# POSCON_PCB.net
KiCad netlist of a schematic drawn in EAGLE
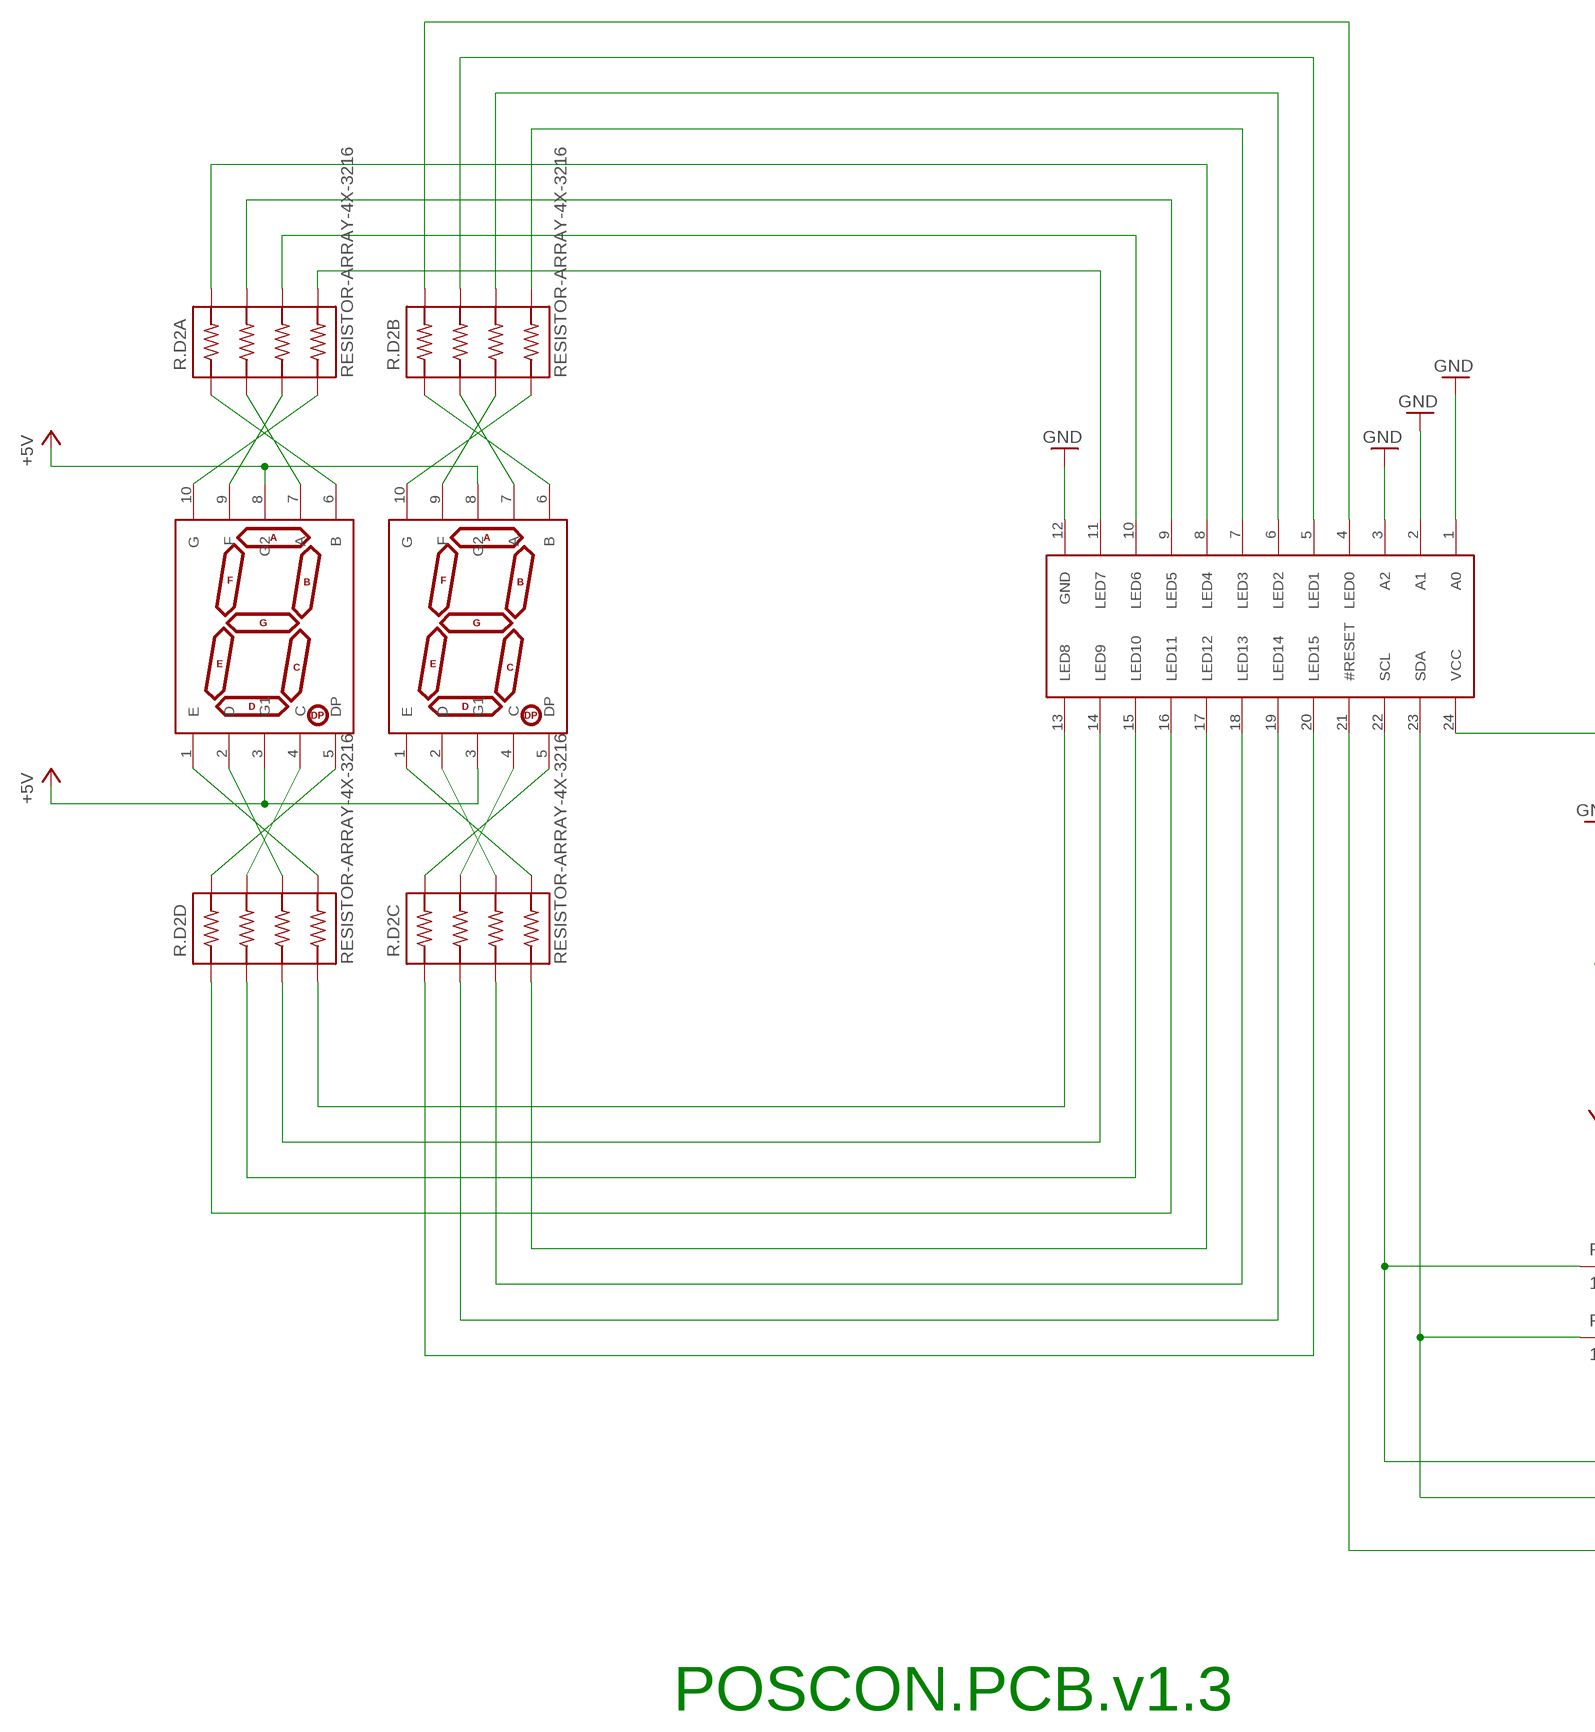
[diagram p0: schematic, sheet 1, part 1 of 2]
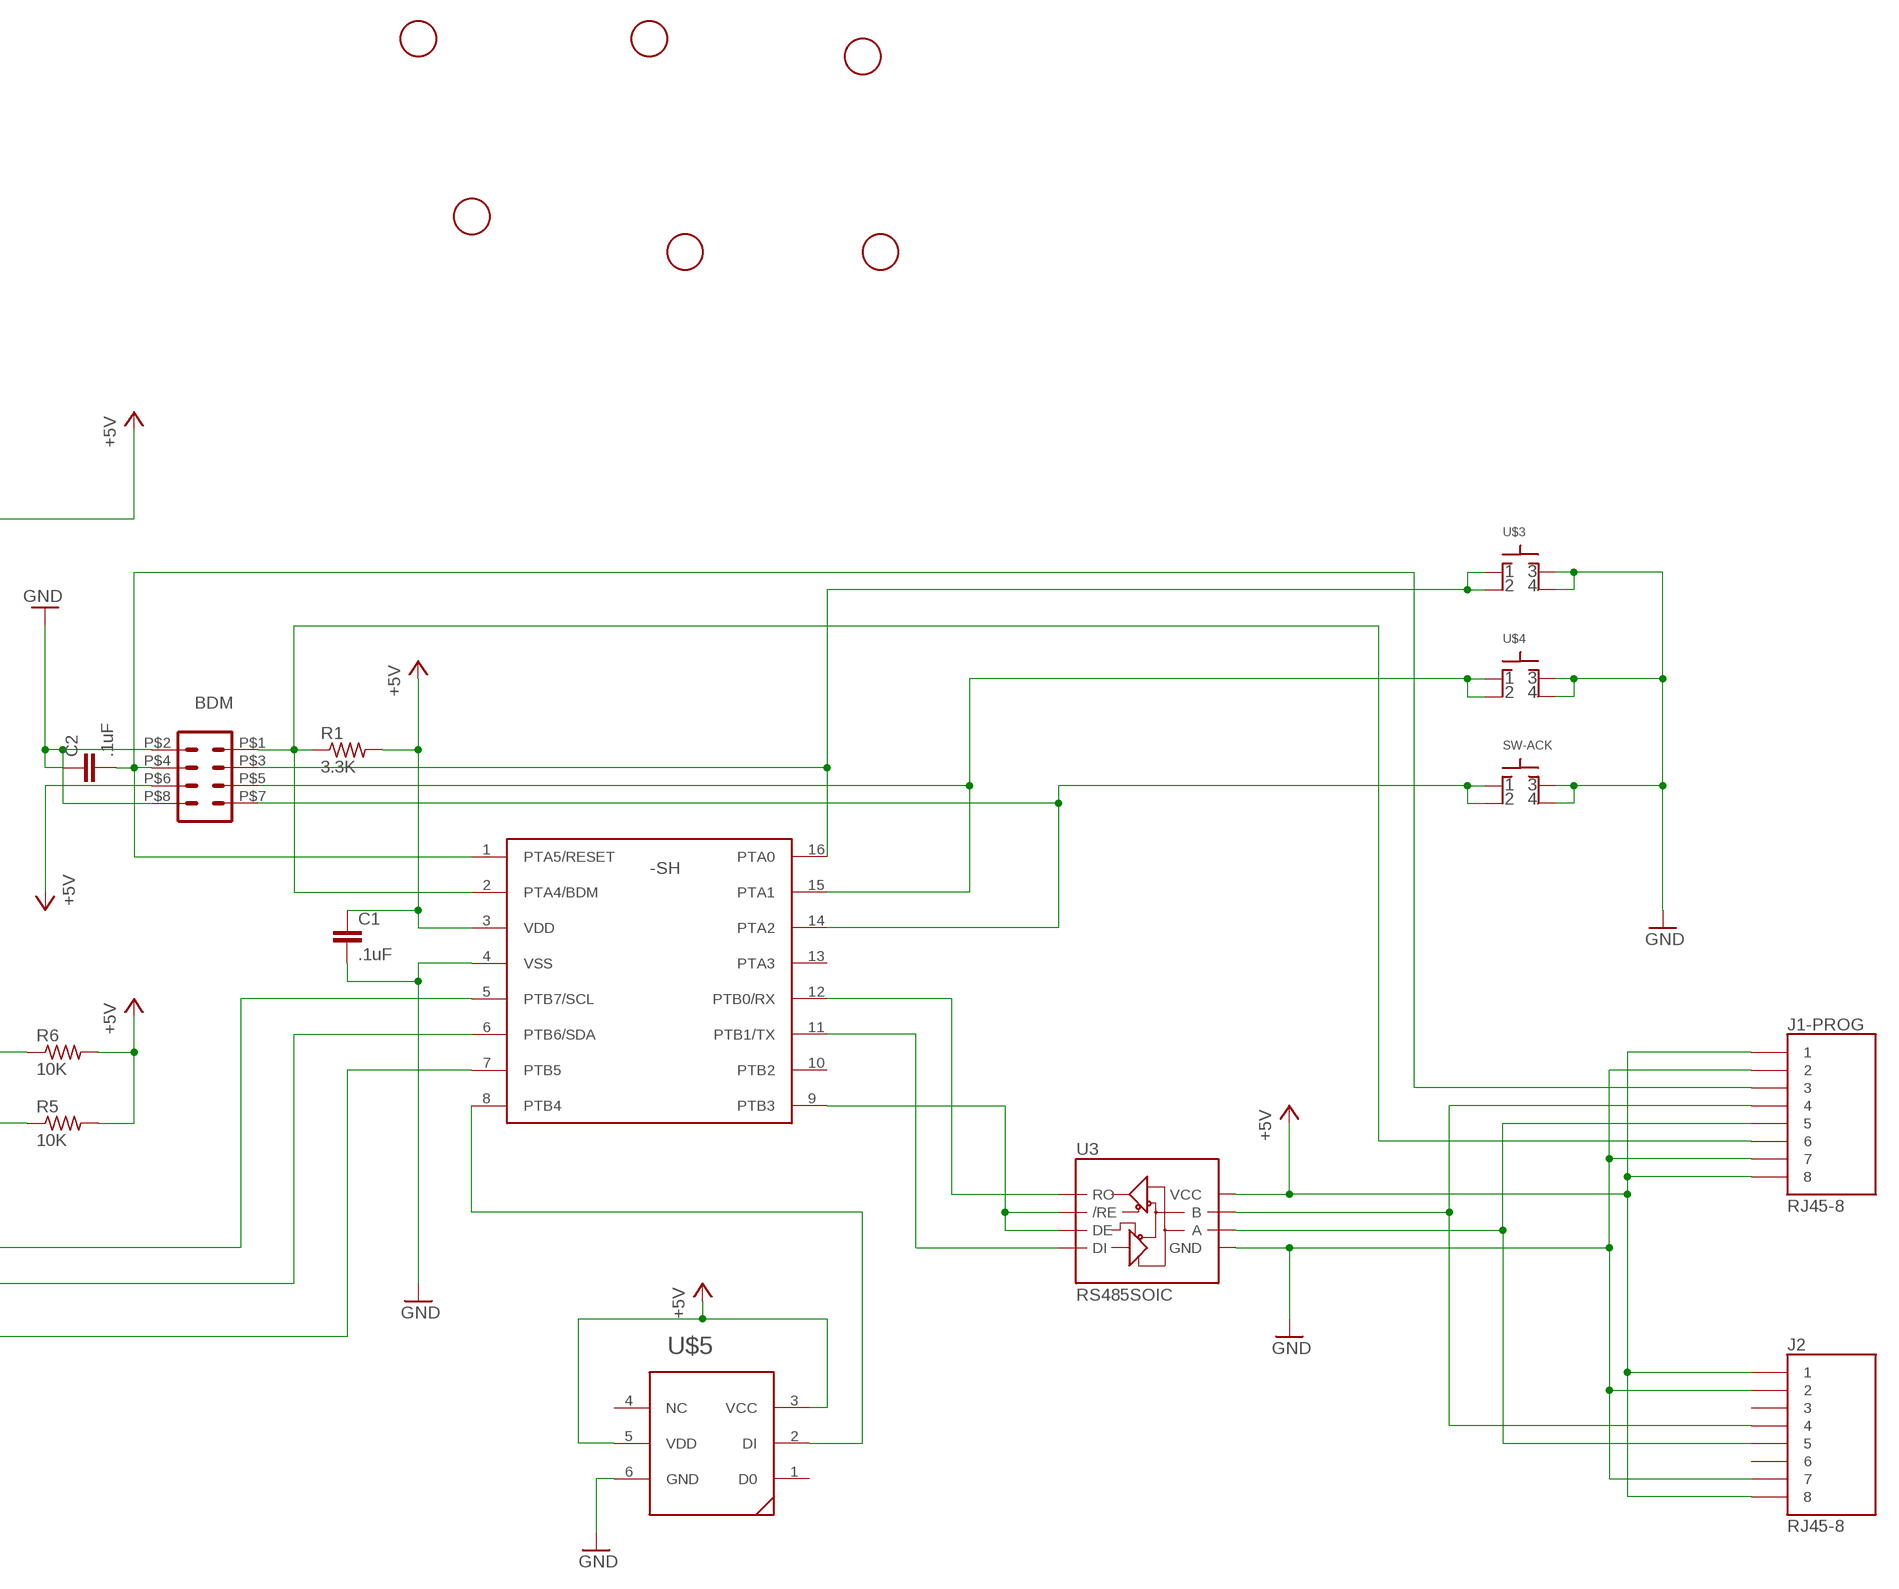
[diagram p1: schematic, sheet 1, part 2 of 2]

(export (version "E")
  (design (tool "Eeschema 10.0.6"))
  (components
    (comp (ref "BDM")
      (value "TP2X4SMD")
      (footprint "eagle-import:SMD4X2")
      (libsource (lib "eagle-import") (part "TP2X4SMD"))
    )
    (comp (ref "C1")
      (value ".1uF")
      (footprint "eagle-import:C0402")
      (libsource (lib "eagle-import") (part "RF-C0402"))
    )
    (comp (ref "C2")
      (value ".1uF")
      (footprint "eagle-import:C0402")
      (libsource (lib "eagle-import") (part "RF-C0402"))
    )
    (comp (ref "J1-PROG")
      (value "RJ45-8")
      (footprint "eagle-import:RJ45_SMD")
      (fields (field (name "MFGN") "Molex") (field (name "MFGP") "0955016889"))
      (libsource (lib "eagle-import") (part "RJ45-8"))
    )
    (comp (ref "J2")
      (value "RJ45-8")
      (footprint "eagle-import:RJ45_SMD")
      (fields (field (name "MFGN") "Molex") (field (name "MFGP") "0955016889"))
      (libsource (lib "eagle-import") (part "RJ45-8"))
    )
    (comp (ref "LED1")
      (value "7SEGMENT-1DIGITSMD")
      (footprint "eagle-import:7SEGMENT-1DIG-.40-SMD")
      (libsource (lib "eagle-import") (part "7SEGMENT-1DIGITSMD"))
    )
    (comp (ref "LED2")
      (value "7SEGMENT-1DIGITSMD")
      (footprint "eagle-import:7SEGMENT-1DIG-.40-SMD")
      (libsource (lib "eagle-import") (part "7SEGMENT-1DIGITSMD"))
    )
    (comp (ref "R.D2A")
      (value "RESISTOR-ARRAY-4X-3216")
      (footprint "eagle-import:3216-4X")
      (libsource (lib "eagle-import") (part "RESISTOR-ARRAY-4X-3216"))
    )
    (comp (ref "R.D2B")
      (value "RESISTOR-ARRAY-4X-3216")
      (footprint "eagle-import:3216-4X")
      (libsource (lib "eagle-import") (part "RESISTOR-ARRAY-4X-3216"))
    )
    (comp (ref "R.D2C")
      (value "RESISTOR-ARRAY-4X-3216")
      (footprint "eagle-import:3216-4X")
      (libsource (lib "eagle-import") (part "RESISTOR-ARRAY-4X-3216"))
    )
    (comp (ref "R.D2D")
      (value "RESISTOR-ARRAY-4X-3216")
      (footprint "eagle-import:3216-4X")
      (libsource (lib "eagle-import") (part "RESISTOR-ARRAY-4X-3216"))
    )
    (comp (ref "R1")
      (value "3.3K")
      (footprint "eagle-import:RF-R0402")
      (libsource (lib "eagle-import") (part "RF-R0402"))
    )
    (comp (ref "R5")
      (value "10K")
      (footprint "eagle-import:RF-R0402")
      (libsource (lib "eagle-import") (part "RF-R0402"))
    )
    (comp (ref "R6")
      (value "10K")
      (footprint "eagle-import:RF-R0402")
      (libsource (lib "eagle-import") (part "RF-R0402"))
    )
    (comp (ref "SW-ACK")
      (value "SWITCH-TACTILE-320.01E11WHT")
      (footprint "eagle-import:SWITCH-TACTILE-320.01E11WHT")
      (fields (field (name "MFGP") "320.01E11WHT"))
      (libsource (lib "eagle-import") (part "SWITCH-TACTILE-320.01E11WHT"))
    )
    (comp (ref "U$1")
      (value "FIDUCIAL")
      (footprint "eagle-import:FIDUCIAL_1MM")
      (libsource (lib "eagle-import") (part "FIDUCIAL"))
    )
    (comp (ref "U$2")
      (value "FIDUCIAL")
      (footprint "eagle-import:FIDUCIAL_1MM")
      (libsource (lib "eagle-import") (part "FIDUCIAL"))
    )
    (comp (ref "U$3")
      (value "SWITCH-TACTILE")
      (footprint "eagle-import:ESWITCH-TL3301PF")
      (libsource (lib "eagle-import") (part "SWITCH-TACTILE"))
    )
    (comp (ref "U$4")
      (value "SWITCH-TACTILE")
      (footprint "eagle-import:ESWITCH-TL3301PF")
      (libsource (lib "eagle-import") (part "SWITCH-TACTILE"))
    )
    (comp (ref "U$5")
      (value "WS2812")
      (footprint "eagle-import:PLCC-6")
      (libsource (lib "eagle-import") (part "WS2812"))
    )
    (comp (ref "U$6")
      (value "FIDUCIAL")
      (footprint "eagle-import:FIDUCIAL_1MM")
      (libsource (lib "eagle-import") (part "FIDUCIAL"))
    )
    (comp (ref "U$7")
      (value "FIDUCIAL")
      (footprint "eagle-import:FIDUCIAL_1MM")
      (libsource (lib "eagle-import") (part "FIDUCIAL"))
    )
    (comp (ref "U$8")
      (value "FIDUCIAL")
      (footprint "eagle-import:FIDUCIAL_1MM")
      (libsource (lib "eagle-import") (part "FIDUCIAL"))
    )
    (comp (ref "U$9")
      (value "FIDUCIAL")
      (footprint "eagle-import:FIDUCIAL_1MM")
      (libsource (lib "eagle-import") (part "FIDUCIAL"))
    )
    (comp (ref "U1")
      (value "MC9S08SH8CTG")
      (footprint "eagle-import:TSSOP16")
      (libsource (lib "eagle-import") (part "MC9S08SH8CTG"))
    )
    (comp (ref "U3")
      (value "RS485SOIC")
      (footprint "eagle-import:SO08")
      (libsource (lib "eagle-import") (part "RS485SOIC"))
    )
    (comp (ref "U4")
      (value "PCA9552")
      (footprint "eagle-import:TSSOP24")
      (fields (field (name "MFGP") "PCA9552PW,112"))
      (libsource (lib "eagle-import") (part "PCA9552"))
    )
  )
  (nets
    (net (code "1") (name "+5V") (class "Default")
      (node (ref "BDM") (pin "P$6") (pinfunction "6_P$6") (pintype "passive"))
      (node (ref "C1") (pin "1") (pinfunction "1_1") (pintype "passive"))
      (node (ref "J1-PROG") (pin "P$1") (pinfunction "1_P$1") (pintype "bidirectional"))
      (node (ref "J1-PROG") (pin "P$8") (pinfunction "8_P$8") (pintype "bidirectional"))
      (node (ref "J2") (pin "P$1") (pinfunction "1_P$1") (pintype "bidirectional"))
      (node (ref "J2") (pin "P$8") (pinfunction "8_P$8") (pintype "bidirectional"))
      (node (ref "LED1") (pin "3") (pinfunction "G1_3") (pintype "bidirectional"))
      (node (ref "LED1") (pin "8") (pinfunction "G2_8") (pintype "bidirectional"))
      (node (ref "LED2") (pin "3") (pinfunction "G1_3") (pintype "bidirectional"))
      (node (ref "LED2") (pin "8") (pinfunction "G2_8") (pintype "bidirectional"))
      (node (ref "R1") (pin "2") (pinfunction "2_2") (pintype "passive"))
      (node (ref "R5") (pin "2") (pinfunction "2_2") (pintype "passive"))
      (node (ref "R6") (pin "2") (pinfunction "2_2") (pintype "passive"))
      (node (ref "U$5") (pin "3") (pinfunction "VCC_3") (pintype "bidirectional"))
      (node (ref "U$5") (pin "5") (pinfunction "VDD_5") (pintype "bidirectional"))
      (node (ref "U1") (pin "3") (pinfunction "VDD_3") (pintype "bidirectional"))
      (node (ref "U3") (pin "8") (pinfunction "VCC_8") (pintype "bidirectional"))
      (node (ref "U4") (pin "24") (pinfunction "VCC_24") (pintype "bidirectional"))
    )
    (net (code "2") (name "GND") (class "Default")
      (node (ref "BDM") (pin "P$2") (pinfunction "2_P$2") (pintype "passive"))
      (node (ref "BDM") (pin "P$8") (pinfunction "8_P$8") (pintype "passive"))
      (node (ref "C1") (pin "2") (pinfunction "2_2") (pintype "passive"))
      (node (ref "C2") (pin "1") (pinfunction "1_1") (pintype "passive"))
      (node (ref "J1-PROG") (pin "P$2") (pinfunction "2_P$2") (pintype "bidirectional"))
      (node (ref "J1-PROG") (pin "P$7") (pinfunction "7_P$7") (pintype "bidirectional"))
      (node (ref "J2") (pin "P$2") (pinfunction "2_P$2") (pintype "bidirectional"))
      (node (ref "J2") (pin "P$7") (pinfunction "7_P$7") (pintype "bidirectional"))
      (node (ref "SW-ACK") (pin "P$3") (pinfunction "3_P$3") (pintype "input"))
      (node (ref "SW-ACK") (pin "P$4") (pinfunction "4_P$4") (pintype "input"))
      (node (ref "U$3") (pin "3") (pinfunction "3_3") (pintype "input"))
      (node (ref "U$3") (pin "4") (pinfunction "4_4") (pintype "input"))
      (node (ref "U$4") (pin "3") (pinfunction "3_3") (pintype "input"))
      (node (ref "U$4") (pin "4") (pinfunction "4_4") (pintype "input"))
      (node (ref "U$5") (pin "6") (pinfunction "GND_6") (pintype "bidirectional"))
      (node (ref "U1") (pin "4") (pinfunction "VSS_4") (pintype "bidirectional"))
      (node (ref "U3") (pin "5") (pinfunction "GND_5") (pintype "bidirectional"))
      (node (ref "U4") (pin "1") (pinfunction "A0_1") (pintype "bidirectional"))
      (node (ref "U4") (pin "12") (pinfunction "GND_12") (pintype "bidirectional"))
      (node (ref "U4") (pin "2") (pinfunction "A1_2") (pintype "bidirectional"))
      (node (ref "U4") (pin "3") (pinfunction "A2_3") (pintype "bidirectional"))
    )
    (net (code "3") (name "Net-(BDM-1)") (class "Default")
      (node (ref "BDM") (pin "P$1") (pinfunction "1_P$1") (pintype "passive"))
      (node (ref "J1-PROG") (pin "P$6") (pinfunction "6_P$6") (pintype "bidirectional"))
      (node (ref "R1") (pin "1") (pinfunction "1_1") (pintype "passive"))
      (node (ref "U1") (pin "2") (pinfunction "PTA4/BDM_2") (pintype "bidirectional"))
    )
    (net (code "4") (name "Net-(BDM-3)") (class "Default")
      (node (ref "BDM") (pin "P$3") (pinfunction "3_P$3") (pintype "passive"))
      (node (ref "U$3") (pin "1") (pinfunction "1_1") (pintype "input"))
      (node (ref "U$3") (pin "2") (pinfunction "2_2") (pintype "input"))
      (node (ref "U1") (pin "16") (pinfunction "PTA0_16") (pintype "bidirectional"))
    )
    (net (code "5") (name "Net-(BDM-4)") (class "Default")
      (node (ref "BDM") (pin "P$4") (pinfunction "4_P$4") (pintype "passive"))
      (node (ref "C2") (pin "2") (pinfunction "2_2") (pintype "passive"))
      (node (ref "J1-PROG") (pin "P$3") (pinfunction "3_P$3") (pintype "bidirectional"))
      (node (ref "U1") (pin "1") (pinfunction "PTA5/RESET_1") (pintype "bidirectional"))
    )
    (net (code "6") (name "Net-(BDM-5)") (class "Default")
      (node (ref "BDM") (pin "P$5") (pinfunction "5_P$5") (pintype "passive"))
      (node (ref "U$4") (pin "1") (pinfunction "1_1") (pintype "input"))
      (node (ref "U$4") (pin "2") (pinfunction "2_2") (pintype "input"))
      (node (ref "U1") (pin "15") (pinfunction "PTA1_15") (pintype "bidirectional"))
    )
    (net (code "7") (name "Net-(BDM-7)") (class "Default")
      (node (ref "BDM") (pin "P$7") (pinfunction "7_P$7") (pintype "passive"))
      (node (ref "SW-ACK") (pin "P$1") (pinfunction "1_P$1") (pintype "input"))
      (node (ref "SW-ACK") (pin "P$2") (pinfunction "2_P$2") (pintype "input"))
      (node (ref "U1") (pin "14") (pinfunction "PTA2_14") (pintype "bidirectional"))
    )
    (net (code "8") (name "Net-(J1-PROG-4)") (class "Default")
      (node (ref "J1-PROG") (pin "P$4") (pinfunction "4_P$4") (pintype "bidirectional"))
      (node (ref "J2") (pin "P$4") (pinfunction "4_P$4") (pintype "bidirectional"))
      (node (ref "U3") (pin "7") (pinfunction "B_7") (pintype "bidirectional"))
    )
    (net (code "9") (name "Net-(J1-PROG-5)") (class "Default")
      (node (ref "J1-PROG") (pin "P$5") (pinfunction "5_P$5") (pintype "bidirectional"))
      (node (ref "J2") (pin "P$5") (pinfunction "5_P$5") (pintype "bidirectional"))
      (node (ref "U3") (pin "6") (pinfunction "A_6") (pintype "bidirectional"))
    )
    (net (code "10") (name "Net-(LED1-A)") (class "Default")
      (node (ref "LED1") (pin "7") (pinfunction "A_7") (pintype "bidirectional"))
      (node (ref "R.D2B") (pin "2") (pinfunction "2A_2") (pintype "passive"))
    )
    (net (code "11") (name "Net-(LED1-B)") (class "Default")
      (node (ref "LED1") (pin "6") (pinfunction "B_6") (pintype "bidirectional"))
      (node (ref "R.D2B") (pin "1") (pinfunction "1A_1") (pintype "passive"))
    )
    (net (code "12") (name "Net-(LED1-C)") (class "Default")
      (node (ref "LED1") (pin "4") (pinfunction "C_4") (pintype "bidirectional"))
      (node (ref "R.D2C") (pin "7") (pinfunction "2B_7") (pintype "passive"))
    )
    (net (code "13") (name "Net-(LED1-D)") (class "Default")
      (node (ref "LED1") (pin "2") (pinfunction "D_2") (pintype "bidirectional"))
      (node (ref "R.D2C") (pin "6") (pinfunction "3B_6") (pintype "passive"))
    )
    (net (code "14") (name "Net-(LED1-DP)") (class "Default")
      (node (ref "LED1") (pin "5") (pinfunction "DP_5") (pintype "bidirectional"))
      (node (ref "R.D2C") (pin "8") (pinfunction "1B_8") (pintype "passive"))
    )
    (net (code "15") (name "Net-(LED1-E)") (class "Default")
      (node (ref "LED1") (pin "1") (pinfunction "E_1") (pintype "bidirectional"))
      (node (ref "R.D2C") (pin "5") (pinfunction "4B_5") (pintype "passive"))
    )
    (net (code "16") (name "Net-(LED1-F)") (class "Default")
      (node (ref "LED1") (pin "9") (pinfunction "F_9") (pintype "bidirectional"))
      (node (ref "R.D2B") (pin "3") (pinfunction "3A_3") (pintype "passive"))
    )
    (net (code "17") (name "Net-(LED1-G)") (class "Default")
      (node (ref "LED1") (pin "10") (pinfunction "G_10") (pintype "bidirectional"))
      (node (ref "R.D2B") (pin "4") (pinfunction "4A_4") (pintype "passive"))
    )
    (net (code "18") (name "Net-(LED2-A)") (class "Default")
      (node (ref "LED2") (pin "7") (pinfunction "A_7") (pintype "bidirectional"))
      (node (ref "R.D2A") (pin "2") (pinfunction "2A_2") (pintype "passive"))
    )
    (net (code "19") (name "Net-(LED2-B)") (class "Default")
      (node (ref "LED2") (pin "6") (pinfunction "B_6") (pintype "bidirectional"))
      (node (ref "R.D2A") (pin "1") (pinfunction "1A_1") (pintype "passive"))
    )
    (net (code "20") (name "Net-(LED2-C)") (class "Default")
      (node (ref "LED2") (pin "4") (pinfunction "C_4") (pintype "bidirectional"))
      (node (ref "R.D2D") (pin "7") (pinfunction "2B_7") (pintype "passive"))
    )
    (net (code "21") (name "Net-(LED2-D)") (class "Default")
      (node (ref "LED2") (pin "2") (pinfunction "D_2") (pintype "bidirectional"))
      (node (ref "R.D2D") (pin "6") (pinfunction "3B_6") (pintype "passive"))
    )
    (net (code "22") (name "Net-(LED2-DP)") (class "Default")
      (node (ref "LED2") (pin "5") (pinfunction "DP_5") (pintype "bidirectional"))
      (node (ref "R.D2D") (pin "8") (pinfunction "1B_8") (pintype "passive"))
    )
    (net (code "23") (name "Net-(LED2-E)") (class "Default")
      (node (ref "LED2") (pin "1") (pinfunction "E_1") (pintype "bidirectional"))
      (node (ref "R.D2D") (pin "5") (pinfunction "4B_5") (pintype "passive"))
    )
    (net (code "24") (name "Net-(LED2-F)") (class "Default")
      (node (ref "LED2") (pin "9") (pinfunction "F_9") (pintype "bidirectional"))
      (node (ref "R.D2A") (pin "3") (pinfunction "3A_3") (pintype "passive"))
    )
    (net (code "25") (name "Net-(LED2-G)") (class "Default")
      (node (ref "LED2") (pin "10") (pinfunction "G_10") (pintype "bidirectional"))
      (node (ref "R.D2A") (pin "4") (pinfunction "4A_4") (pintype "passive"))
    )
    (net (code "26") (name "Net-(R.D2A-1B)") (class "Default")
      (node (ref "R.D2A") (pin "8") (pinfunction "1B_8") (pintype "passive"))
      (node (ref "U4") (pin "8") (pinfunction "LED4_8") (pintype "bidirectional"))
    )
    (net (code "27") (name "Net-(R.D2A-2B)") (class "Default")
      (node (ref "R.D2A") (pin "7") (pinfunction "2B_7") (pintype "passive"))
      (node (ref "U4") (pin "9") (pinfunction "LED5_9") (pintype "bidirectional"))
    )
    (net (code "28") (name "Net-(R.D2A-3B)") (class "Default")
      (node (ref "R.D2A") (pin "6") (pinfunction "3B_6") (pintype "passive"))
      (node (ref "U4") (pin "10") (pinfunction "LED6_10") (pintype "bidirectional"))
    )
    (net (code "29") (name "Net-(R.D2A-4B)") (class "Default")
      (node (ref "R.D2A") (pin "5") (pinfunction "4B_5") (pintype "passive"))
      (node (ref "U4") (pin "11") (pinfunction "LED7_11") (pintype "bidirectional"))
    )
    (net (code "30") (name "Net-(R.D2B-1B)") (class "Default")
      (node (ref "R.D2B") (pin "8") (pinfunction "1B_8") (pintype "passive"))
      (node (ref "U4") (pin "4") (pinfunction "LED0_4") (pintype "bidirectional"))
    )
    (net (code "31") (name "Net-(R.D2B-2B)") (class "Default")
      (node (ref "R.D2B") (pin "7") (pinfunction "2B_7") (pintype "passive"))
      (node (ref "U4") (pin "5") (pinfunction "LED1_5") (pintype "bidirectional"))
    )
    (net (code "32") (name "Net-(R.D2B-3B)") (class "Default")
      (node (ref "R.D2B") (pin "6") (pinfunction "3B_6") (pintype "passive"))
      (node (ref "U4") (pin "6") (pinfunction "LED2_6") (pintype "bidirectional"))
    )
    (net (code "33") (name "Net-(R.D2B-4B)") (class "Default")
      (node (ref "R.D2B") (pin "5") (pinfunction "4B_5") (pintype "passive"))
      (node (ref "U4") (pin "7") (pinfunction "LED3_7") (pintype "bidirectional"))
    )
    (net (code "34") (name "Net-(R.D2C-1A)") (class "Default")
      (node (ref "R.D2C") (pin "1") (pinfunction "1A_1") (pintype "passive"))
      (node (ref "U4") (pin "20") (pinfunction "LED15_20") (pintype "bidirectional"))
    )
    (net (code "35") (name "Net-(R.D2C-2A)") (class "Default")
      (node (ref "R.D2C") (pin "2") (pinfunction "2A_2") (pintype "passive"))
      (node (ref "U4") (pin "19") (pinfunction "LED14_19") (pintype "bidirectional"))
    )
    (net (code "36") (name "Net-(R.D2C-3A)") (class "Default")
      (node (ref "R.D2C") (pin "3") (pinfunction "3A_3") (pintype "passive"))
      (node (ref "U4") (pin "18") (pinfunction "LED13_18") (pintype "bidirectional"))
    )
    (net (code "37") (name "Net-(R.D2C-4A)") (class "Default")
      (node (ref "R.D2C") (pin "4") (pinfunction "4A_4") (pintype "passive"))
      (node (ref "U4") (pin "17") (pinfunction "LED12_17") (pintype "bidirectional"))
    )
    (net (code "38") (name "Net-(R.D2D-1A)") (class "Default")
      (node (ref "R.D2D") (pin "1") (pinfunction "1A_1") (pintype "passive"))
      (node (ref "U4") (pin "16") (pinfunction "LED11_16") (pintype "bidirectional"))
    )
    (net (code "39") (name "Net-(R.D2D-2A)") (class "Default")
      (node (ref "R.D2D") (pin "2") (pinfunction "2A_2") (pintype "passive"))
      (node (ref "U4") (pin "15") (pinfunction "LED10_15") (pintype "bidirectional"))
    )
    (net (code "40") (name "Net-(R.D2D-3A)") (class "Default")
      (node (ref "R.D2D") (pin "3") (pinfunction "3A_3") (pintype "passive"))
      (node (ref "U4") (pin "14") (pinfunction "LED9_14") (pintype "bidirectional"))
    )
    (net (code "41") (name "Net-(R.D2D-4A)") (class "Default")
      (node (ref "R.D2D") (pin "4") (pinfunction "4A_4") (pintype "passive"))
      (node (ref "U4") (pin "13") (pinfunction "LED8_13") (pintype "bidirectional"))
    )
    (net (code "42") (name "Net-(U$5-DI)") (class "Default")
      (node (ref "U$5") (pin "2") (pinfunction "DI_2") (pintype "bidirectional"))
      (node (ref "U1") (pin "8") (pinfunction "PTB4_8") (pintype "bidirectional"))
    )
    (net (code "43") (name "Net-(U1-PTB0{slash}RX)") (class "Default")
      (node (ref "U1") (pin "12") (pinfunction "PTB0/RX_12") (pintype "bidirectional"))
      (node (ref "U3") (pin "1") (pinfunction "RO_1") (pintype "bidirectional"))
    )
    (net (code "44") (name "Net-(U1-PTB1{slash}TX)") (class "Default")
      (node (ref "U1") (pin "11") (pinfunction "PTB1/TX_11") (pintype "bidirectional"))
      (node (ref "U3") (pin "4") (pinfunction "DI_4") (pintype "bidirectional"))
    )
    (net (code "45") (name "Net-(U1-PTB3)") (class "Default")
      (node (ref "U1") (pin "9") (pinfunction "PTB3_9") (pintype "bidirectional"))
      (node (ref "U3") (pin "2") (pinfunction "/RE_2") (pintype "bidirectional"))
      (node (ref "U3") (pin "3") (pinfunction "DE_3") (pintype "bidirectional"))
    )
    (net (code "46") (name "Net-(U1-PTB5)") (class "Default")
      (node (ref "U1") (pin "7") (pinfunction "PTB5_7") (pintype "bidirectional"))
      (node (ref "U4") (pin "21") (pinfunction "#RESET_21") (pintype "bidirectional"))
    )
    (net (code "47") (name "Net-(U1-PTB6{slash}SDA)") (class "Default")
      (node (ref "R5") (pin "1") (pinfunction "1_1") (pintype "passive"))
      (node (ref "U1") (pin "6") (pinfunction "PTB6/SDA_6") (pintype "bidirectional"))
      (node (ref "U4") (pin "23") (pinfunction "SDA_23") (pintype "bidirectional"))
    )
    (net (code "48") (name "Net-(U1-PTB7{slash}SCL)") (class "Default")
      (node (ref "R6") (pin "1") (pinfunction "1_1") (pintype "passive"))
      (node (ref "U1") (pin "5") (pinfunction "PTB7/SCL_5") (pintype "bidirectional"))
      (node (ref "U4") (pin "22") (pinfunction "SCL_22") (pintype "bidirectional"))
    )
    (net (code "49") (name "unconnected-(J2-3-PadP$3)") (class "Default")
      (node (ref "J2") (pin "P$3") (pinfunction "3_P$3") (pintype "bidirectional"))
    )
    (net (code "50") (name "unconnected-(J2-6-PadP$6)") (class "Default")
      (node (ref "J2") (pin "P$6") (pinfunction "6_P$6") (pintype "bidirectional"))
    )
    (net (code "51") (name "unconnected-(U$5-D0-Pad1)") (class "Default")
      (node (ref "U$5") (pin "1") (pinfunction "D0_1") (pintype "bidirectional"))
    )
    (net (code "52") (name "unconnected-(U$5-NC-Pad4)") (class "Default")
      (node (ref "U$5") (pin "4") (pinfunction "NC_4") (pintype "bidirectional"))
    )
    (net (code "53") (name "unconnected-(U1-PTA3-Pad13)") (class "Default")
      (node (ref "U1") (pin "13") (pinfunction "PTA3_13") (pintype "bidirectional"))
    )
    (net (code "54") (name "unconnected-(U1-PTB2-Pad10)") (class "Default")
      (node (ref "U1") (pin "10") (pinfunction "PTB2_10") (pintype "bidirectional"))
    )
  )
)
